# SunriseClockMainv3.net
KiCad netlist of a schematic drawn in EAGLE
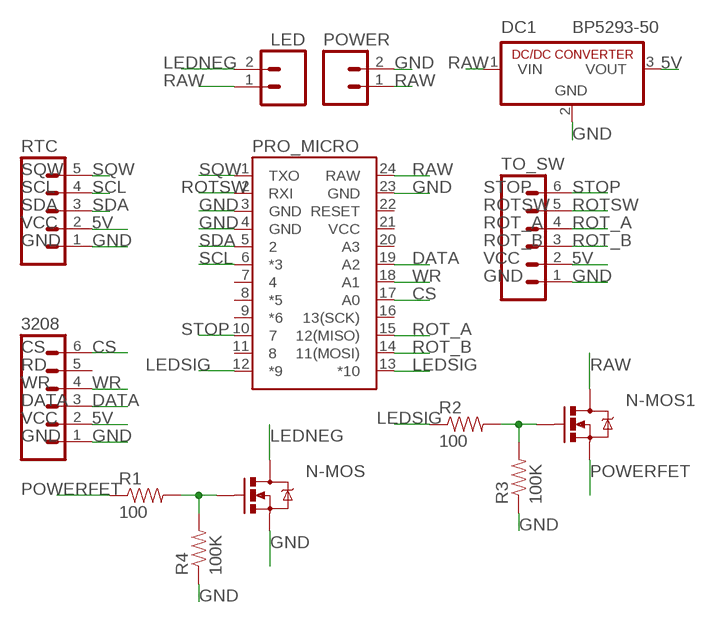
[diagram p0: schematic, sheet 1]

(export (version "E")
  (design (tool "Eeschema 10.0.6"))
  (components
    (comp (ref "3208")
      (value "M06LOCK")
      (footprint "eagle-import:1X06_LOCK")
      (libsource (lib "eagle-import") (part "M06LOCK"))
    )
    (comp (ref "DC1")
      (value "BP5293-50")
      (footprint "eagle-import:SIP3")
      (libsource (lib "eagle-import") (part "R-78C-1.05.0"))
    )
    (comp (ref "LED")
      (value "M02LOCK")
      (footprint "eagle-import:1X02_LOCK")
      (libsource (lib "eagle-import") (part "M02LOCK"))
    )
    (comp (ref "N-MOS")
      (value "MOSFET-NCHANNELFQP30N06L")
      (footprint "eagle-import:TO220V")
      (libsource (lib "eagle-import") (part "MOSFET-NCHANNELFQP30N06L"))
    )
    (comp (ref "N-MOS1")
      (value "MOSFET-NCHANNELFQP30N06L")
      (footprint "eagle-import:TO220V")
      (libsource (lib "eagle-import") (part "MOSFET-NCHANNELFQP30N06L"))
    )
    (comp (ref "POWER")
      (value "M025MM")
      (footprint "eagle-import:SCREWTERMINAL-5MM-2")
      (libsource (lib "eagle-import") (part "M025MM"))
    )
    (comp (ref "PRO_MICRO")
      (value "ARDUINO_PRO_MICRO")
      (footprint "eagle-import:ARDUINO_PRO_MICRO")
      (libsource (lib "eagle-import") (part "ARDUINO_PRO_MICRO"))
    )
    (comp (ref "R1")
      (value "100")
      (footprint "eagle-import:AXIAL-0.4")
      (libsource (lib "eagle-import") (part "RESISTORPTH-1/4W"))
    )
    (comp (ref "R2")
      (value "100")
      (footprint "eagle-import:AXIAL-0.4")
      (libsource (lib "eagle-import") (part "RESISTORPTH-1/4W"))
    )
    (comp (ref "R3")
      (value "100K")
      (footprint "eagle-import:AXIAL-0.4")
      (libsource (lib "eagle-import") (part "RESISTORPTH-1/4W"))
    )
    (comp (ref "R4")
      (value "100K")
      (footprint "eagle-import:AXIAL-0.4")
      (libsource (lib "eagle-import") (part "RESISTORPTH-1/4W"))
    )
    (comp (ref "RTC")
      (value "M05LOCK")
      (footprint "eagle-import:1X05_LOCK")
      (libsource (lib "eagle-import") (part "M05LOCK"))
    )
    (comp (ref "TO_SW")
      (value "M06LOCK")
      (footprint "eagle-import:1X06_LOCK")
      (libsource (lib "eagle-import") (part "M06LOCK"))
    )
  )
  (nets
    (net (code "1") (name "/5V") (class "Default")
      (node (ref "3208") (pin "2") (pinfunction "2_2") (pintype "passive"))
      (node (ref "DC1") (pin "3") (pinfunction "VOUT_3") (pintype "passive"))
      (node (ref "RTC") (pin "2") (pinfunction "2_2") (pintype "passive"))
      (node (ref "TO_SW") (pin "2") (pinfunction "2_2") (pintype "passive"))
    )
    (net (code "2") (name "/CS") (class "Default")
      (node (ref "3208") (pin "6") (pinfunction "6_6") (pintype "passive"))
      (node (ref "PRO_MICRO") (pin "17") (pinfunction "A0_17") (pintype "bidirectional"))
    )
    (net (code "3") (name "/DATA") (class "Default")
      (node (ref "3208") (pin "3") (pinfunction "3_3") (pintype "passive"))
      (node (ref "PRO_MICRO") (pin "19") (pinfunction "A2_19") (pintype "bidirectional"))
    )
    (net (code "4") (name "/GND") (class "Default")
      (node (ref "3208") (pin "1") (pinfunction "1_1") (pintype "passive"))
      (node (ref "DC1") (pin "2") (pinfunction "GND_2") (pintype "passive"))
      (node (ref "N-MOS") (pin "3") (pinfunction "S_3") (pintype "passive"))
      (node (ref "POWER") (pin "2") (pinfunction "2_2") (pintype "passive"))
      (node (ref "PRO_MICRO") (pin "23") (pinfunction "GND_23") (pintype "bidirectional"))
      (node (ref "PRO_MICRO") (pin "3") (pinfunction "GND_3") (pintype "bidirectional"))
      (node (ref "PRO_MICRO") (pin "4") (pinfunction "GND_4") (pintype "bidirectional"))
      (node (ref "R3") (pin "P$1") (pinfunction "1_P$1") (pintype "passive"))
      (node (ref "R4") (pin "P$1") (pinfunction "1_P$1") (pintype "passive"))
      (node (ref "RTC") (pin "1") (pinfunction "1_1") (pintype "passive"))
      (node (ref "TO_SW") (pin "1") (pinfunction "1_1") (pintype "passive"))
    )
    (net (code "5") (name "/LEDNEG") (class "Default")
      (node (ref "LED") (pin "2") (pinfunction "2_2") (pintype "passive"))
      (node (ref "N-MOS") (pin "2") (pinfunction "D_2") (pintype "passive"))
    )
    (net (code "6") (name "/LEDSIG") (class "Default")
      (node (ref "PRO_MICRO") (pin "12") (pinfunction "*9_12") (pintype "bidirectional"))
      (node (ref "PRO_MICRO") (pin "13") (pinfunction "*10_13") (pintype "bidirectional"))
      (node (ref "R2") (pin "P$1") (pinfunction "1_P$1") (pintype "passive"))
    )
    (net (code "7") (name "/POWERFET") (class "Default")
      (node (ref "N-MOS1") (pin "3") (pinfunction "S_3") (pintype "passive"))
      (node (ref "R1") (pin "P$1") (pinfunction "1_P$1") (pintype "passive"))
    )
    (net (code "8") (name "/RAW") (class "Default")
      (node (ref "DC1") (pin "1") (pinfunction "VIN_1") (pintype "passive"))
      (node (ref "LED") (pin "1") (pinfunction "1_1") (pintype "passive"))
      (node (ref "N-MOS1") (pin "2") (pinfunction "D_2") (pintype "passive"))
      (node (ref "POWER") (pin "1") (pinfunction "1_1") (pintype "passive"))
      (node (ref "PRO_MICRO") (pin "24") (pinfunction "RAW_24") (pintype "bidirectional"))
    )
    (net (code "9") (name "/ROTSW") (class "Default")
      (node (ref "PRO_MICRO") (pin "2") (pinfunction "RXI_2") (pintype "bidirectional"))
      (node (ref "TO_SW") (pin "5") (pinfunction "5_5") (pintype "passive"))
    )
    (net (code "10") (name "/ROT_A") (class "Default")
      (node (ref "PRO_MICRO") (pin "15") (pinfunction "12(MISO)_15") (pintype "bidirectional"))
      (node (ref "TO_SW") (pin "4") (pinfunction "4_4") (pintype "passive"))
    )
    (net (code "11") (name "/ROT_B") (class "Default")
      (node (ref "PRO_MICRO") (pin "14") (pinfunction "11(MOSI)_14") (pintype "bidirectional"))
      (node (ref "TO_SW") (pin "3") (pinfunction "3_3") (pintype "passive"))
    )
    (net (code "12") (name "/SCL") (class "Default")
      (node (ref "PRO_MICRO") (pin "6") (pinfunction "*3_6") (pintype "bidirectional"))
      (node (ref "RTC") (pin "4") (pinfunction "4_4") (pintype "passive"))
    )
    (net (code "13") (name "/SDA") (class "Default")
      (node (ref "PRO_MICRO") (pin "5") (pinfunction "2_5") (pintype "bidirectional"))
      (node (ref "RTC") (pin "3") (pinfunction "3_3") (pintype "passive"))
    )
    (net (code "14") (name "/SQW") (class "Default")
      (node (ref "PRO_MICRO") (pin "1") (pinfunction "TXO_1") (pintype "bidirectional"))
      (node (ref "RTC") (pin "5") (pinfunction "5_5") (pintype "passive"))
    )
    (net (code "15") (name "/STOP") (class "Default")
      (node (ref "PRO_MICRO") (pin "10") (pinfunction "7_10") (pintype "bidirectional"))
      (node (ref "TO_SW") (pin "6") (pinfunction "6_6") (pintype "passive"))
    )
    (net (code "16") (name "/WR") (class "Default")
      (node (ref "3208") (pin "4") (pinfunction "4_4") (pintype "passive"))
      (node (ref "PRO_MICRO") (pin "18") (pinfunction "A1_18") (pintype "bidirectional"))
    )
    (net (code "17") (name "Net-(N-MOS-G)") (class "Default")
      (node (ref "N-MOS") (pin "1") (pinfunction "G_1") (pintype "passive"))
      (node (ref "R1") (pin "P$2") (pinfunction "2_P$2") (pintype "passive"))
      (node (ref "R4") (pin "P$2") (pinfunction "2_P$2") (pintype "passive"))
    )
    (net (code "18") (name "Net-(N-MOS1-G)") (class "Default")
      (node (ref "N-MOS1") (pin "1") (pinfunction "G_1") (pintype "passive"))
      (node (ref "R2") (pin "P$2") (pinfunction "2_P$2") (pintype "passive"))
      (node (ref "R3") (pin "P$2") (pinfunction "2_P$2") (pintype "passive"))
    )
    (net (code "19") (name "unconnected-(3208-Pad5)") (class "Default")
      (node (ref "3208") (pin "5") (pinfunction "5_5") (pintype "passive"))
    )
    (net (code "20") (name "unconnected-(PRO_MICRO-*5-Pad8)") (class "Default")
      (node (ref "PRO_MICRO") (pin "8") (pinfunction "*5_8") (pintype "bidirectional"))
    )
    (net (code "21") (name "unconnected-(PRO_MICRO-*6-Pad9)") (class "Default")
      (node (ref "PRO_MICRO") (pin "9") (pinfunction "*6_9") (pintype "bidirectional"))
    )
    (net (code "22") (name "unconnected-(PRO_MICRO-4-Pad7)") (class "Default")
      (node (ref "PRO_MICRO") (pin "7") (pinfunction "4_7") (pintype "bidirectional"))
    )
    (net (code "23") (name "unconnected-(PRO_MICRO-8-Pad11)") (class "Default")
      (node (ref "PRO_MICRO") (pin "11") (pinfunction "8_11") (pintype "bidirectional"))
    )
    (net (code "24") (name "unconnected-(PRO_MICRO-13(SCK)-Pad16)") (class "Default")
      (node (ref "PRO_MICRO") (pin "16") (pinfunction "13(SCK)_16") (pintype "bidirectional"))
    )
    (net (code "25") (name "unconnected-(PRO_MICRO-A3-Pad20)") (class "Default")
      (node (ref "PRO_MICRO") (pin "20") (pinfunction "A3_20") (pintype "bidirectional"))
    )
    (net (code "26") (name "unconnected-(PRO_MICRO-RESET-Pad22)") (class "Default")
      (node (ref "PRO_MICRO") (pin "22") (pinfunction "RESET_22") (pintype "bidirectional"))
    )
    (net (code "27") (name "unconnected-(PRO_MICRO-VCC-Pad21)") (class "Default")
      (node (ref "PRO_MICRO") (pin "21") (pinfunction "VCC_21") (pintype "bidirectional"))
    )
  )
)
